# PDM-S01-V00-PSU.net
KiCad netlist of a schematic drawn in Altium Designer
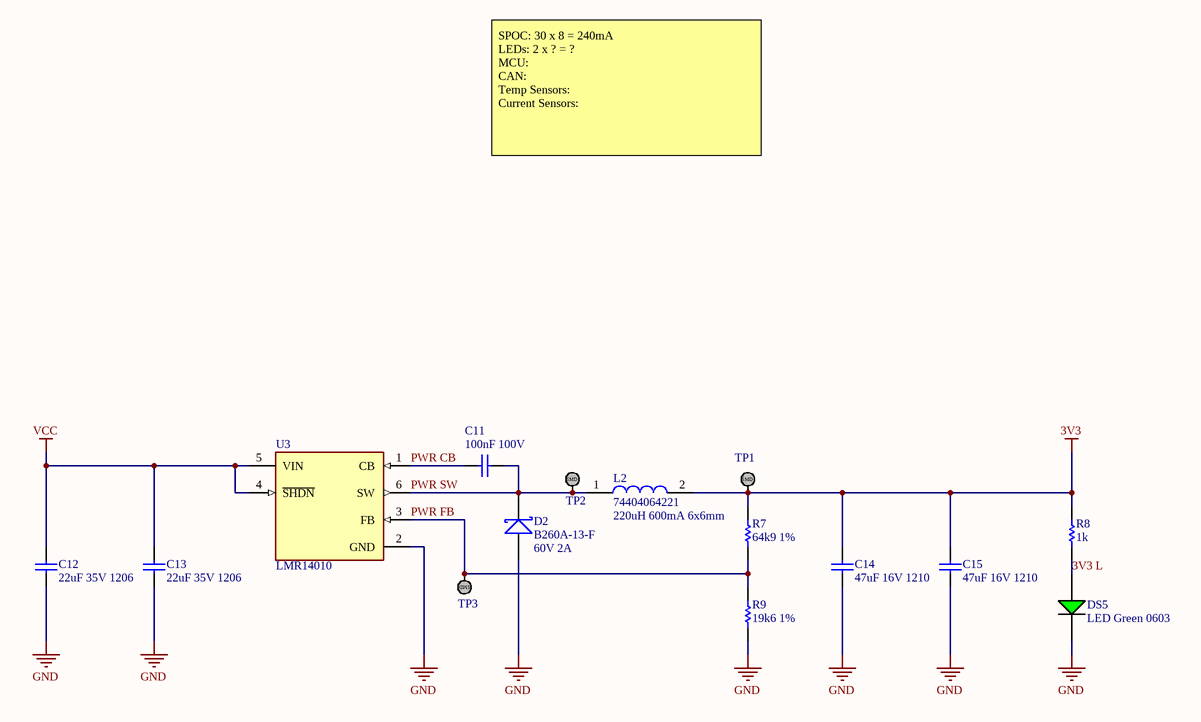
[diagram p0: PDM-S01-V00-PSU.SchDoc]

(export (version "E")
  (design (tool "Eeschema 10.0.6"))
  (components
    (comp (ref "C11")
      (value "100nF 100V")
      (footprint "Cap_Ceramic_0603")
      (description "Capacitor, Ceramic, SMD, 100nF, 100V, 5%, X7R, 0603")
      (libsource (lib "StandardCapacitors") (part "100nF 100V 5% X7R 0603"))
    )
    (comp (ref "C12")
      (value "22uF 35V 1206")
      (footprint "Cap_Ceramic_1206")
      (description "Capacitor, Ceramic, SMD, 22uF, 35V, 10%, X7R, 1206")
      (libsource (lib "StandardCapacitors") (part "22uF 35V 10% X7R 1206"))
    )
    (comp (ref "C13")
      (value "22uF 35V 1206")
      (footprint "Cap_Ceramic_1206")
      (description "Capacitor, Ceramic, SMD, 22uF, 35V, 10%, X7R, 1206")
      (libsource (lib "StandardCapacitors") (part "22uF 35V 10% X7R 1206"))
    )
    (comp (ref "C14")
      (value "47uF 16V 1210")
      (footprint "Cap_Ceramic_1210")
      (description "Capacitor, Ceramic, SMD, 47uF, 16V, 5%, X7R, 1210")
      (libsource (lib "StandardCapacitors") (part "47uF 16V 10% X7R 1210"))
    )
    (comp (ref "C15")
      (value "47uF 16V 1210")
      (footprint "Cap_Ceramic_1210")
      (description "Capacitor, Ceramic, SMD, 47uF, 16V, 5%, X7R, 1210")
      (libsource (lib "StandardCapacitors") (part "47uF 16V 10% X7R 1210"))
    )
    (comp (ref "D2")
      (value "B260A-13-F")
      (footprint "SMA")
      (description "Diode, Schottky Barrier Rectifier, 60 V, 2 A, B260A-13-F")
      (libsource (lib "QUTMS_DiodeLibrary") (part "B260A-13-F"))
    )
    (comp (ref "DS5")
      (value "LED Green 0603")
      (footprint "LED GREEN 0603")
      (libsource (lib "QUTMS_LEDLibrary") (part "LED Green 0603"))
    )
    (comp (ref "L2")
      (value "74404064221")
      (footprint "Inductor_6x6mm")
      (description "FIXED IND 220UH 660MA 850 MOHM")
      (libsource (lib "QUTMS_InductorLibrary") (part "74404064221"))
    )
    (comp (ref "R7")
      (value "64k9 1%")
      (footprint "Res_ThinFilm_0603")
      (description "Resistor, SMD, 64k9, 0.1W, 5%, 0603")
      (libsource (lib "StandardResistors") (part "64k9 1% 0603"))
    )
    (comp (ref "R8")
      (value "1k")
      (footprint "Res_ThinFilm_0603")
      (description "Resistor, SMD, 1k, 0.1W, 5%, 0603")
      (libsource (lib "StandardResistors") (part "1k 5% 0603"))
    )
    (comp (ref "R9")
      (value "19k6 1%")
      (footprint "Res_ThinFilm_0603")
      (description "Resistor, SMD, 19k6, 0.1W, 5%, 0603")
      (libsource (lib "StandardResistors") (part "19k6 1% 0603"))
    )
    (comp (ref "TP1")
      (value "TestPoint_SMD")
      (footprint "TestPointSMD")
      (libsource (lib "StandardTest") (part "TestPoint_SMD"))
    )
    (comp (ref "TP2")
      (value "TestPoint_SMD")
      (footprint "TestPointSMD")
      (libsource (lib "StandardTest") (part "TestPoint_SMD"))
    )
    (comp (ref "TP3")
      (value "TestPoint_SMD")
      (footprint "TestPointSMD")
      (libsource (lib "StandardTest") (part "TestPoint_SMD"))
    )
    (comp (ref "U3")
      (value "LMR14010")
      (footprint "LMR14010")
      (libsource (lib "QUTMS_PowerSupplyLibrary") (part "LMR14010"))
    )
  )
  (nets
    (net (code "1") (name "/3V3 L") (class "Default")
      (node (ref "DS5") (pin "1") (pinfunction "A_1") (pintype "passive"))
      (node (ref "R8") (pin "1") (pinfunction "1_1") (pintype "passive"))
    )
    (net (code "2") (name "/PWR CB") (class "Default")
      (node (ref "C11") (pin "1") (pinfunction "1_1") (pintype "passive"))
      (node (ref "U3") (pin "1") (pinfunction "CB_1") (pintype "input"))
    )
    (net (code "3") (name "/PWR FB") (class "Default")
      (node (ref "R7") (pin "1") (pinfunction "1_1") (pintype "passive"))
      (node (ref "R9") (pin "2") (pinfunction "2_2") (pintype "passive"))
      (node (ref "TP3") (pin "1") (pinfunction "1_1") (pintype "passive"))
      (node (ref "U3") (pin "3") (pinfunction "FB_3") (pintype "input"))
    )
    (net (code "4") (name "/PWR SW") (class "Default")
      (node (ref "C11") (pin "2") (pinfunction "2_2") (pintype "passive"))
      (node (ref "D2") (pin "K") (pinfunction "K_K") (pintype "passive"))
      (node (ref "L2") (pin "1") (pinfunction "1_1") (pintype "passive"))
      (node (ref "TP2") (pin "1") (pinfunction "1_1") (pintype "passive"))
      (node (ref "U3") (pin "6") (pinfunction "SW_6") (pintype "output"))
    )
    (net (code "5") (name "3V3") (class "Default")
      (node (ref "C14") (pin "2") (pinfunction "2_2") (pintype "passive"))
      (node (ref "C15") (pin "2") (pinfunction "2_2") (pintype "passive"))
      (node (ref "L2") (pin "2") (pinfunction "2_2") (pintype "passive"))
      (node (ref "R7") (pin "2") (pinfunction "2_2") (pintype "passive"))
      (node (ref "R8") (pin "2") (pinfunction "2_2") (pintype "passive"))
      (node (ref "TP1") (pin "1") (pinfunction "1_1") (pintype "passive"))
    )
    (net (code "6") (name "GND") (class "Default")
      (node (ref "C12") (pin "1") (pinfunction "1_1") (pintype "passive"))
      (node (ref "C13") (pin "1") (pinfunction "1_1") (pintype "passive"))
      (node (ref "C14") (pin "1") (pinfunction "1_1") (pintype "passive"))
      (node (ref "C15") (pin "1") (pinfunction "1_1") (pintype "passive"))
      (node (ref "D2") (pin "A") (pinfunction "A_A") (pintype "passive"))
      (node (ref "DS5") (pin "2") (pinfunction "C_2") (pintype "passive"))
      (node (ref "R9") (pin "1") (pinfunction "1_1") (pintype "passive"))
      (node (ref "U3") (pin "2") (pinfunction "GND_2") (pintype "power_in"))
    )
    (net (code "7") (name "VCC") (class "Default")
      (node (ref "C12") (pin "2") (pinfunction "2_2") (pintype "passive"))
      (node (ref "C13") (pin "2") (pinfunction "2_2") (pintype "passive"))
      (node (ref "U3") (pin "4") (pinfunction "~{SHDN}_4") (pintype "input"))
      (node (ref "U3") (pin "5") (pinfunction "VIN_5") (pintype "power_in"))
    )
  )
)
